# internal_excitation.net
KiCad netlist of a schematic drawn in EAGLE
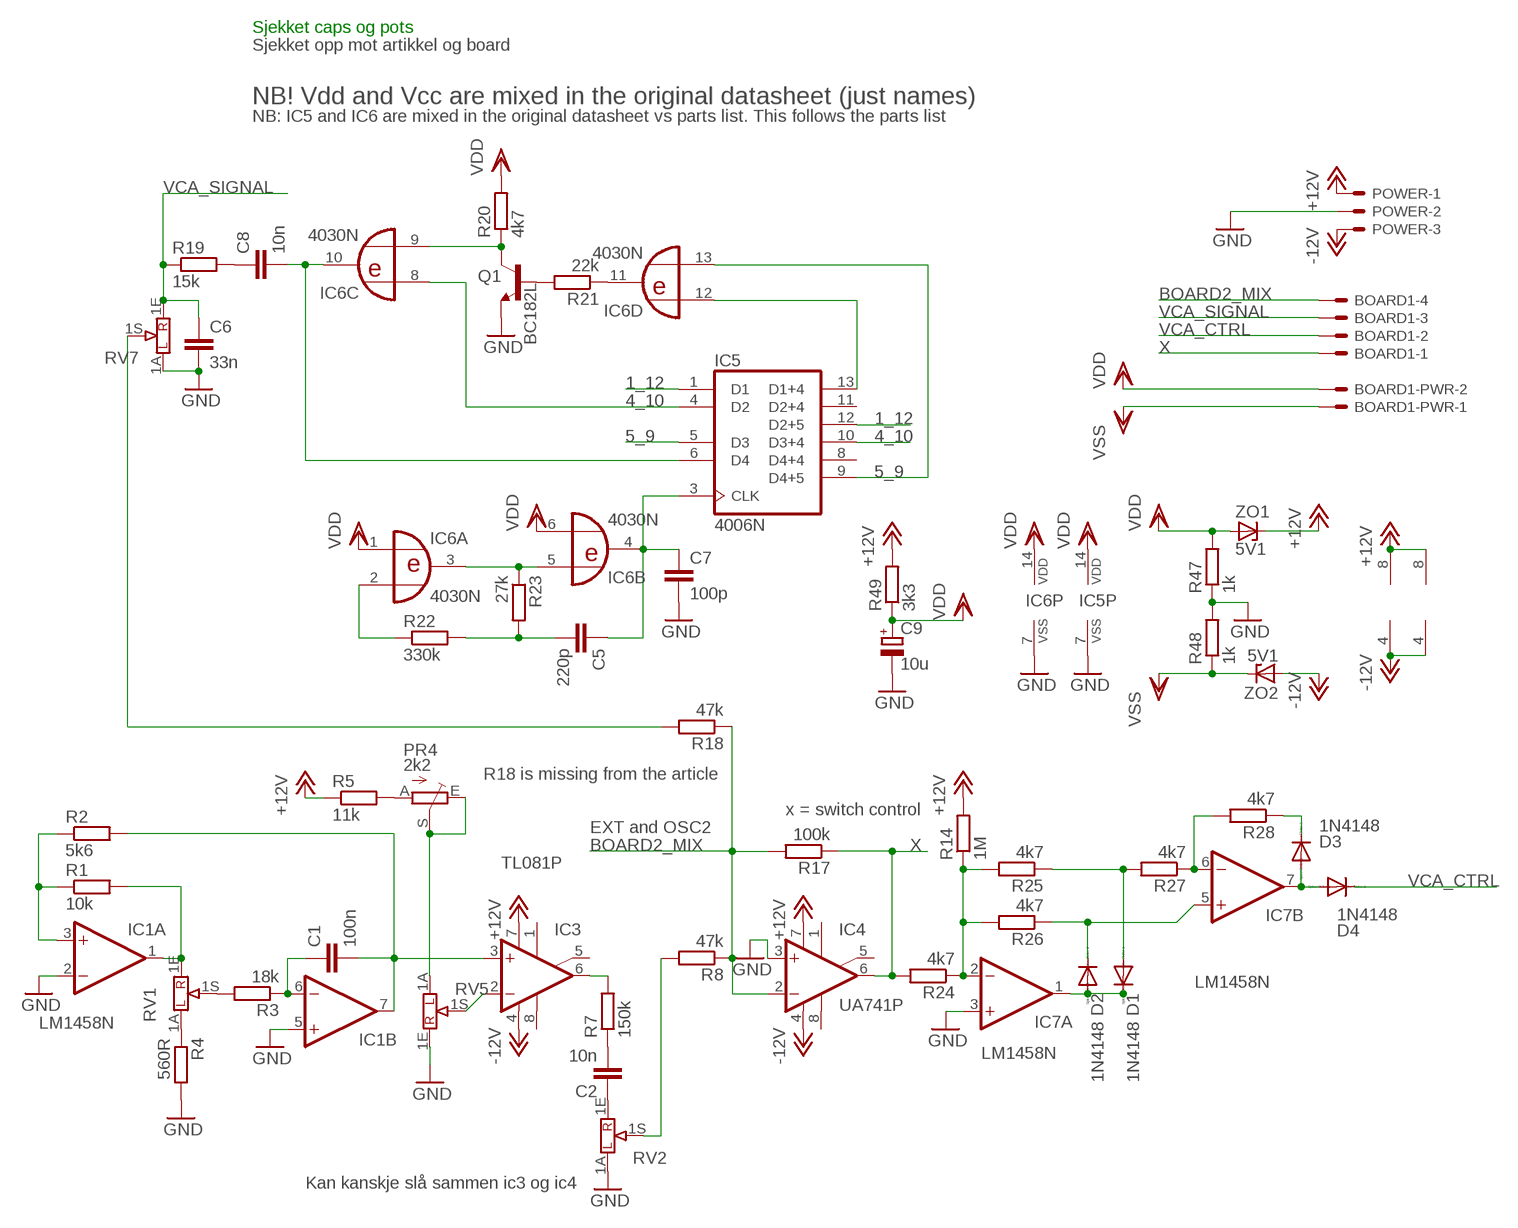
[diagram p0: schematic, sheet 1]

(export (version "E")
  (design (tool "Eeschema 10.0.6"))
  (components
    (comp (ref "BOARD1")
      (value "22-23-2041")
      (footprint "eagle-import:22-23-2041")
      (fields (field (name "MF") "MOLEX"))
      (libsource (lib "eagle-import") (part "22-23-2041"))
    )
    (comp (ref "BOARD1-PWR")
      (value "22-23-2021")
      (footprint "eagle-import:22-23-2021")
      (fields (field (name "MF") "MOLEX"))
      (libsource (lib "eagle-import") (part "22-23-2021"))
    )
    (comp (ref "C1")
      (value "100n")
      (footprint "eagle-import:C075-032X103")
      (libsource (lib "eagle-import") (part "C-EU075-032X103"))
    )
    (comp (ref "C2")
      (value "10n")
      (footprint "eagle-import:C025-025X050")
      (libsource (lib "eagle-import") (part "C-EU025-025X050"))
    )
    (comp (ref "C5")
      (value "220p")
      (footprint "eagle-import:C025-025X050")
      (libsource (lib "eagle-import") (part "C-EU025-025X050"))
    )
    (comp (ref "C6")
      (value "33n")
      (footprint "eagle-import:C075-032X103")
      (libsource (lib "eagle-import") (part "C-EU075-032X103"))
    )
    (comp (ref "C7")
      (value "100p")
      (footprint "eagle-import:C025-025X050")
      (libsource (lib "eagle-import") (part "C-EU025-025X050"))
    )
    (comp (ref "C8")
      (value "10n")
      (footprint "eagle-import:C075-032X103")
      (libsource (lib "eagle-import") (part "C-EU075-032X103"))
    )
    (comp (ref "C9")
      (value "10u")
      (footprint "eagle-import:E2,5-5")
      (libsource (lib "eagle-import") (part "CPOL-EUE2.5-5"))
    )
    (comp (ref "D1")
      (value "1N4148")
      (footprint "eagle-import:DO35-5J")
      (libsource (lib "eagle-import") (part "1N4148DOJ35-5"))
    )
    (comp (ref "D2")
      (value "1N4148")
      (footprint "eagle-import:DO35-5J")
      (libsource (lib "eagle-import") (part "1N4148DOJ35-5"))
    )
    (comp (ref "D3")
      (value "1N4148")
      (footprint "eagle-import:DO35-5J")
      (libsource (lib "eagle-import") (part "1N4148DOJ35-5"))
    )
    (comp (ref "D4")
      (value "1N4148")
      (footprint "eagle-import:DO35-5J")
      (libsource (lib "eagle-import") (part "1N4148DOJ35-5"))
    )
    (comp (ref "IC1")
      (value "LM1458N")
      (footprint "eagle-import:DIL08")
      (libsource (lib "eagle-import") (part "1458NLM"))
    )
    (comp (ref "IC3")
      (value "TL081P")
      (footprint "eagle-import:DIL08")
      (libsource (lib "eagle-import") (part "TL081P"))
    )
    (comp (ref "IC4")
      (value "UA741P")
      (footprint "eagle-import:DIL08")
      (libsource (lib "eagle-import") (part "741PUA"))
    )
    (comp (ref "IC5")
      (value "4006N")
      (footprint "eagle-import:DIL14")
      (libsource (lib "eagle-import") (part "4006N"))
    )
    (comp (ref "IC6")
      (value "4030N")
      (footprint "eagle-import:DIL14")
      (libsource (lib "eagle-import") (part "4030N"))
    )
    (comp (ref "IC7")
      (value "LM1458N")
      (footprint "eagle-import:DIL08")
      (libsource (lib "eagle-import") (part "1458NLM"))
    )
    (comp (ref "POWER")
      (value "KK-156-3")
      (footprint "eagle-import:KK-156-3")
      (libsource (lib "eagle-import") (part "KK-156-3"))
    )
    (comp (ref "PR4")
      (value "2k2")
      (footprint "eagle-import:CA9V")
      (libsource (lib "eagle-import") (part "TRIM_EU-CA9V"))
    )
    (comp (ref "Q1")
      (value "BC182L")
      (footprint "eagle-import:TO92-ECB")
      (libsource (lib "eagle-import") (part "-NPN-TO92-ECB"))
    )
    (comp (ref "R1")
      (value "10k")
      (footprint "eagle-import:0207_7")
      (libsource (lib "eagle-import") (part "R-EU_0207/7"))
    )
    (comp (ref "R2")
      (value "5k6")
      (footprint "eagle-import:0207_7")
      (libsource (lib "eagle-import") (part "R-EU_0207/7"))
    )
    (comp (ref "R3")
      (value "18k")
      (footprint "eagle-import:0207_7")
      (libsource (lib "eagle-import") (part "R-EU_0207/7"))
    )
    (comp (ref "R4")
      (value "560R")
      (footprint "eagle-import:0207_7")
      (libsource (lib "eagle-import") (part "R-EU_0207/7"))
    )
    (comp (ref "R5")
      (value "11k")
      (footprint "eagle-import:0207_7")
      (libsource (lib "eagle-import") (part "R-EU_0207/7"))
    )
    (comp (ref "R7")
      (value "150k")
      (footprint "eagle-import:0207_7")
      (libsource (lib "eagle-import") (part "R-EU_0207/7"))
    )
    (comp (ref "R8")
      (value "47k")
      (footprint "eagle-import:0207_7")
      (libsource (lib "eagle-import") (part "R-EU_0207/7"))
    )
    (comp (ref "R14")
      (value "1M")
      (footprint "eagle-import:0207_7")
      (libsource (lib "eagle-import") (part "R-EU_0207/7"))
    )
    (comp (ref "R17")
      (value "100k")
      (footprint "eagle-import:0207_7")
      (libsource (lib "eagle-import") (part "R-EU_0207/7"))
    )
    (comp (ref "R18")
      (value "47k")
      (footprint "eagle-import:0207_7")
      (libsource (lib "eagle-import") (part "R-EU_0207/7"))
    )
    (comp (ref "R19")
      (value "15k")
      (footprint "eagle-import:0207_7")
      (libsource (lib "eagle-import") (part "R-EU_0207/7"))
    )
    (comp (ref "R20")
      (value "4k7")
      (footprint "eagle-import:0207_7")
      (libsource (lib "eagle-import") (part "R-EU_0207/7"))
    )
    (comp (ref "R21")
      (value "22k")
      (footprint "eagle-import:0207_7")
      (libsource (lib "eagle-import") (part "R-EU_0207/7"))
    )
    (comp (ref "R22")
      (value "330k")
      (footprint "eagle-import:0207_7")
      (libsource (lib "eagle-import") (part "R-EU_0207/7"))
    )
    (comp (ref "R23")
      (value "27k")
      (footprint "eagle-import:0207_7")
      (libsource (lib "eagle-import") (part "R-EU_0207/7"))
    )
    (comp (ref "R24")
      (value "4k7")
      (footprint "eagle-import:0207_7")
      (libsource (lib "eagle-import") (part "R-EU_0207/7"))
    )
    (comp (ref "R25")
      (value "4k7")
      (footprint "eagle-import:0207_7")
      (libsource (lib "eagle-import") (part "R-EU_0207/7"))
    )
    (comp (ref "R26")
      (value "4k7")
      (footprint "eagle-import:0207_7")
      (libsource (lib "eagle-import") (part "R-EU_0207/7"))
    )
    (comp (ref "R27")
      (value "4k7")
      (footprint "eagle-import:0207_7")
      (libsource (lib "eagle-import") (part "R-EU_0207/7"))
    )
    (comp (ref "R28")
      (value "4k7")
      (footprint "eagle-import:0207_7")
      (libsource (lib "eagle-import") (part "R-EU_0207/7"))
    )
    (comp (ref "R47")
      (value "1k")
      (footprint "eagle-import:0207_7")
      (libsource (lib "eagle-import") (part "R-EU_0207/7"))
    )
    (comp (ref "R48")
      (value "1k")
      (footprint "eagle-import:0207_7")
      (libsource (lib "eagle-import") (part "R-EU_0207/7"))
    )
    (comp (ref "R49")
      (value "3k3")
      (footprint "eagle-import:0207_7")
      (libsource (lib "eagle-import") (part "R-EU_0207/7"))
    )
    (comp (ref "RV1")
      (value "10k log")
      (footprint "eagle-import:POT16_W_BRACKET")
      (libsource (lib "eagle-import") (part "POT16_W_BRACKET{dblquote}{dblquote}"))
    )
    (comp (ref "RV2")
      (value "10k log")
      (footprint "eagle-import:POT16_W_BRACKET")
      (libsource (lib "eagle-import") (part "POT16_W_BRACKET{dblquote}{dblquote}"))
    )
    (comp (ref "RV5")
      (value "10k")
      (footprint "eagle-import:POT16_W_BRACKET")
      (libsource (lib "eagle-import") (part "POT16_W_BRACKET{dblquote}{dblquote}"))
    )
    (comp (ref "RV7")
      (value "10k")
      (footprint "eagle-import:POT16_W_BRACKET")
      (libsource (lib "eagle-import") (part "POT16_W_BRACKET{dblquote}{dblquote}"))
    )
    (comp (ref "ZO1")
      (value "5V1")
      (footprint "eagle-import:ZDIO-5")
      (libsource (lib "eagle-import") (part "ZENER-DIODEZD-5"))
    )
    (comp (ref "ZO2")
      (value "5V1")
      (footprint "eagle-import:ZDIO-5")
      (libsource (lib "eagle-import") (part "ZENER-DIODEZD-5"))
    )
  )
  (nets
    (net (code "1") (name "+12V") (class "Default")
      (node (ref "IC1") (pin "8") (pinfunction "V+_8") (pintype "power_in"))
      (node (ref "IC3") (pin "7") (pinfunction "V+_7") (pintype "power_in"))
      (node (ref "IC4") (pin "7") (pinfunction "V+_7") (pintype "power_in"))
      (node (ref "IC7") (pin "8") (pinfunction "V+_8") (pintype "power_in"))
      (node (ref "POWER") (pin "1") (pinfunction "S_1") (pintype "passive"))
      (node (ref "R14") (pin "2") (pinfunction "2_2") (pintype "passive"))
      (node (ref "R49") (pin "2") (pinfunction "2_2") (pintype "passive"))
      (node (ref "R5") (pin "1") (pinfunction "1_1") (pintype "passive"))
      (node (ref "ZO1") (pin "C") (pinfunction "C_C") (pintype "passive"))
    )
    (net (code "2") (name "-12V") (class "Default")
      (node (ref "IC1") (pin "4") (pinfunction "V-_4") (pintype "power_in"))
      (node (ref "IC3") (pin "4") (pinfunction "V-_4") (pintype "power_in"))
      (node (ref "IC4") (pin "4") (pinfunction "V-_4") (pintype "power_in"))
      (node (ref "IC7") (pin "4") (pinfunction "V-_4") (pintype "power_in"))
      (node (ref "POWER") (pin "3") (pinfunction "S_3") (pintype "passive"))
      (node (ref "ZO2") (pin "A") (pinfunction "A_A") (pintype "passive"))
    )
    (net (code "3") (name "/1_12") (class "Default")
      (node (ref "IC5") (pin "1") (pinfunction "D1_1") (pintype "input"))
      (node (ref "IC5") (pin "12") (pinfunction "D2+5_12") (pintype "output"))
    )
    (net (code "4") (name "/4_10") (class "Default")
      (node (ref "IC5") (pin "10") (pinfunction "D3+4_10") (pintype "output"))
      (node (ref "IC5") (pin "4") (pinfunction "D2_4") (pintype "input"))
      (node (ref "IC6") (pin "8") (pinfunction "I0_8") (pintype "input"))
    )
    (net (code "5") (name "/5_9") (class "Default")
      (node (ref "IC5") (pin "5") (pinfunction "D3_5") (pintype "input"))
      (node (ref "IC5") (pin "9") (pinfunction "D4+5_9") (pintype "output"))
      (node (ref "IC6") (pin "13") (pinfunction "I1_13") (pintype "input"))
    )
    (net (code "6") (name "/BOARD2_MIX") (class "Default")
      (node (ref "BOARD1") (pin "4") (pinfunction "S_4") (pintype "passive"))
      (node (ref "IC4") (pin "2") (pinfunction "-IN_2") (pintype "input"))
      (node (ref "R17") (pin "2") (pinfunction "2_2") (pintype "passive"))
      (node (ref "R18") (pin "1") (pinfunction "1_1") (pintype "passive"))
      (node (ref "R8") (pin "1") (pinfunction "1_1") (pintype "passive"))
    )
    (net (code "7") (name "/VCA_CTRL") (class "Default")
      (node (ref "BOARD1") (pin "2") (pinfunction "S_2") (pintype "passive"))
      (node (ref "D4") (pin "C") (pinfunction "C_C") (pintype "passive"))
    )
    (net (code "8") (name "/VCA_SIGNAL") (class "Default")
      (node (ref "BOARD1") (pin "3") (pinfunction "S_3") (pintype "passive"))
      (node (ref "C6") (pin "1") (pinfunction "1_1") (pintype "passive"))
      (node (ref "R19") (pin "1") (pinfunction "1_1") (pintype "passive"))
      (node (ref "RV7") (pin "1E") (pinfunction "1E_1E") (pintype "passive"))
    )
    (net (code "9") (name "/X") (class "Default")
      (node (ref "BOARD1") (pin "1") (pinfunction "S_1") (pintype "passive"))
      (node (ref "IC4") (pin "6") (pinfunction "OUT_6") (pintype "output"))
      (node (ref "R17") (pin "1") (pinfunction "1_1") (pintype "passive"))
      (node (ref "R24") (pin "2") (pinfunction "2_2") (pintype "passive"))
    )
    (net (code "10") (name "GND") (class "Default")
      (node (ref "C6") (pin "2") (pinfunction "2_2") (pintype "passive"))
      (node (ref "C7") (pin "2") (pinfunction "2_2") (pintype "passive"))
      (node (ref "C9") (pin "-") (pinfunction "-_-") (pintype "passive"))
      (node (ref "IC1") (pin "2") (pinfunction "-IN_2") (pintype "input"))
      (node (ref "IC1") (pin "5") (pinfunction "+IN_5") (pintype "input"))
      (node (ref "IC4") (pin "3") (pinfunction "+IN_3") (pintype "input"))
      (node (ref "IC5") (pin "7") (pinfunction "VSS_7") (pintype "power_in"))
      (node (ref "IC6") (pin "7") (pinfunction "VSS_7") (pintype "power_in"))
      (node (ref "IC7") (pin "3") (pinfunction "+IN_3") (pintype "input"))
      (node (ref "POWER") (pin "2") (pinfunction "S_2") (pintype "passive"))
      (node (ref "Q1") (pin "E") (pinfunction "E_E") (pintype "passive"))
      (node (ref "R4") (pin "2") (pinfunction "2_2") (pintype "passive"))
      (node (ref "R47") (pin "1") (pinfunction "1_1") (pintype "passive"))
      (node (ref "R48") (pin "2") (pinfunction "2_2") (pintype "passive"))
      (node (ref "RV2") (pin "1A") (pinfunction "1A_1A") (pintype "passive"))
      (node (ref "RV5") (pin "1E") (pinfunction "1E_1E") (pintype "passive"))
      (node (ref "RV7") (pin "1A") (pinfunction "1A_1A") (pintype "passive"))
    )
    (net (code "11") (name "Net-(C2-Pad1)") (class "Default")
      (node (ref "C2") (pin "1") (pinfunction "1_1") (pintype "passive"))
      (node (ref "RV2") (pin "1E") (pinfunction "1E_1E") (pintype "passive"))
    )
    (net (code "12") (name "Net-(C2-Pad2)") (class "Default")
      (node (ref "C2") (pin "2") (pinfunction "2_2") (pintype "passive"))
      (node (ref "R7") (pin "1") (pinfunction "1_1") (pintype "passive"))
    )
    (net (code "13") (name "Net-(C5-Pad2)") (class "Default")
      (node (ref "C5") (pin "2") (pinfunction "2_2") (pintype "passive"))
      (node (ref "R22") (pin "2") (pinfunction "2_2") (pintype "passive"))
      (node (ref "R23") (pin "2") (pinfunction "2_2") (pintype "passive"))
    )
    (net (code "14") (name "Net-(C8-Pad1)") (class "Default")
      (node (ref "C8") (pin "1") (pinfunction "1_1") (pintype "passive"))
      (node (ref "R19") (pin "2") (pinfunction "2_2") (pintype "passive"))
    )
    (net (code "15") (name "Net-(D1-PadA)") (class "Default")
      (node (ref "D1") (pin "A") (pinfunction "A_A") (pintype "passive"))
      (node (ref "R25") (pin "1") (pinfunction "1_1") (pintype "passive"))
      (node (ref "R27") (pin "2") (pinfunction "2_2") (pintype "passive"))
    )
    (net (code "16") (name "Net-(D3-PadC)") (class "Default")
      (node (ref "D3") (pin "C") (pinfunction "C_C") (pintype "passive"))
      (node (ref "R28") (pin "1") (pinfunction "1_1") (pintype "passive"))
    )
    (net (code "17") (name "Net-(IC1A-+IN)") (class "Default")
      (node (ref "IC1") (pin "3") (pinfunction "+IN_3") (pintype "input"))
      (node (ref "R1") (pin "1") (pinfunction "1_1") (pintype "passive"))
      (node (ref "R2") (pin "1") (pinfunction "1_1") (pintype "passive"))
    )
    (net (code "18") (name "Net-(IC1A-OUT)") (class "Default")
      (node (ref "IC1") (pin "1") (pinfunction "OUT_1") (pintype "output"))
      (node (ref "R1") (pin "2") (pinfunction "2_2") (pintype "passive"))
      (node (ref "RV1") (pin "1E") (pinfunction "1E_1E") (pintype "passive"))
    )
    (net (code "19") (name "Net-(IC1B--IN)") (class "Default")
      (node (ref "C1") (pin "1") (pinfunction "1_1") (pintype "passive"))
      (node (ref "IC1") (pin "6") (pinfunction "-IN_6") (pintype "input"))
      (node (ref "R3") (pin "1") (pinfunction "1_1") (pintype "passive"))
    )
    (net (code "20") (name "Net-(IC1B-OUT)") (class "Default")
      (node (ref "C1") (pin "2") (pinfunction "2_2") (pintype "passive"))
      (node (ref "IC1") (pin "7") (pinfunction "OUT_7") (pintype "output"))
      (node (ref "IC3") (pin "3") (pinfunction "+IN_3") (pintype "input"))
      (node (ref "R2") (pin "2") (pinfunction "2_2") (pintype "passive"))
    )
    (net (code "21") (name "Net-(IC3--IN)") (class "Default")
      (node (ref "IC3") (pin "2") (pinfunction "-IN_2") (pintype "input"))
      (node (ref "RV5") (pin "1S") (pinfunction "1S_1S") (pintype "passive"))
    )
    (net (code "22") (name "Net-(IC3-OUT)") (class "Default")
      (node (ref "IC3") (pin "6") (pinfunction "OUT_6") (pintype "output"))
      (node (ref "R7") (pin "2") (pinfunction "2_2") (pintype "passive"))
    )
    (net (code "23") (name "Net-(IC5A-CLK)") (class "Default")
      (node (ref "C5") (pin "1") (pinfunction "1_1") (pintype "passive"))
      (node (ref "C7") (pin "1") (pinfunction "1_1") (pintype "passive"))
      (node (ref "IC5") (pin "3") (pinfunction "CLK_3") (pintype "input"))
      (node (ref "IC6") (pin "4") (pinfunction "O_4") (pintype "output"))
    )
    (net (code "24") (name "Net-(IC5A-D1+4)") (class "Default")
      (node (ref "IC5") (pin "13") (pinfunction "D1+4_13") (pintype "output"))
      (node (ref "IC6") (pin "12") (pinfunction "I0_12") (pintype "input"))
    )
    (net (code "25") (name "Net-(IC5A-D4)") (class "Default")
      (node (ref "C8") (pin "2") (pinfunction "2_2") (pintype "passive"))
      (node (ref "IC5") (pin "6") (pinfunction "D4_6") (pintype "input"))
      (node (ref "IC6") (pin "10") (pinfunction "O_10") (pintype "output"))
    )
    (net (code "26") (name "Net-(IC6A-I1)") (class "Default")
      (node (ref "IC6") (pin "2") (pinfunction "I1_2") (pintype "input"))
      (node (ref "R22") (pin "1") (pinfunction "1_1") (pintype "passive"))
    )
    (net (code "27") (name "Net-(IC6A-O)") (class "Default")
      (node (ref "IC6") (pin "3") (pinfunction "O_3") (pintype "output"))
      (node (ref "IC6") (pin "5") (pinfunction "I0_5") (pintype "input"))
      (node (ref "R23") (pin "1") (pinfunction "1_1") (pintype "passive"))
    )
    (net (code "28") (name "Net-(IC6C-I1)") (class "Default")
      (node (ref "IC6") (pin "9") (pinfunction "I1_9") (pintype "input"))
      (node (ref "Q1") (pin "C") (pinfunction "C_C") (pintype "passive"))
      (node (ref "R20") (pin "1") (pinfunction "1_1") (pintype "passive"))
    )
    (net (code "29") (name "Net-(IC6D-O)") (class "Default")
      (node (ref "IC6") (pin "11") (pinfunction "O_11") (pintype "output"))
      (node (ref "R21") (pin "1") (pinfunction "1_1") (pintype "passive"))
    )
    (net (code "30") (name "Net-(IC7A--IN)") (class "Default")
      (node (ref "IC7") (pin "2") (pinfunction "-IN_2") (pintype "input"))
      (node (ref "R14") (pin "1") (pinfunction "1_1") (pintype "passive"))
      (node (ref "R24") (pin "1") (pinfunction "1_1") (pintype "passive"))
      (node (ref "R25") (pin "2") (pinfunction "2_2") (pintype "passive"))
      (node (ref "R26") (pin "2") (pinfunction "2_2") (pintype "passive"))
    )
    (net (code "31") (name "Net-(IC7A-OUT)") (class "Default")
      (node (ref "D1") (pin "C") (pinfunction "C_C") (pintype "passive"))
      (node (ref "D2") (pin "A") (pinfunction "A_A") (pintype "passive"))
      (node (ref "IC7") (pin "1") (pinfunction "OUT_1") (pintype "output"))
    )
    (net (code "32") (name "Net-(IC7B-+IN)") (class "Default")
      (node (ref "D2") (pin "C") (pinfunction "C_C") (pintype "passive"))
      (node (ref "IC7") (pin "5") (pinfunction "+IN_5") (pintype "input"))
      (node (ref "R26") (pin "1") (pinfunction "1_1") (pintype "passive"))
    )
    (net (code "33") (name "Net-(IC7B--IN)") (class "Default")
      (node (ref "IC7") (pin "6") (pinfunction "-IN_6") (pintype "input"))
      (node (ref "R27") (pin "1") (pinfunction "1_1") (pintype "passive"))
      (node (ref "R28") (pin "2") (pinfunction "2_2") (pintype "passive"))
    )
    (net (code "34") (name "Net-(IC7B-OUT)") (class "Default")
      (node (ref "D3") (pin "A") (pinfunction "A_A") (pintype "passive"))
      (node (ref "D4") (pin "A") (pinfunction "A_A") (pintype "passive"))
      (node (ref "IC7") (pin "7") (pinfunction "OUT_7") (pintype "output"))
    )
    (net (code "35") (name "Net-(PR4-PadA)") (class "Default")
      (node (ref "PR4") (pin "A") (pinfunction "A_A") (pintype "passive"))
      (node (ref "R5") (pin "2") (pinfunction "2_2") (pintype "passive"))
    )
    (net (code "36") (name "Net-(PR4-PadE)") (class "Default")
      (node (ref "PR4") (pin "E") (pinfunction "E_E") (pintype "passive"))
      (node (ref "PR4") (pin "S") (pinfunction "S_S") (pintype "passive"))
      (node (ref "RV5") (pin "1A") (pinfunction "1A_1A") (pintype "passive"))
    )
    (net (code "37") (name "Net-(Q1-PadB)") (class "Default")
      (node (ref "Q1") (pin "B") (pinfunction "B_B") (pintype "passive"))
      (node (ref "R21") (pin "2") (pinfunction "2_2") (pintype "passive"))
    )
    (net (code "38") (name "Net-(R3-Pad2)") (class "Default")
      (node (ref "R3") (pin "2") (pinfunction "2_2") (pintype "passive"))
      (node (ref "RV1") (pin "1S") (pinfunction "1S_1S") (pintype "passive"))
    )
    (net (code "39") (name "Net-(R4-Pad1)") (class "Default")
      (node (ref "R4") (pin "1") (pinfunction "1_1") (pintype "passive"))
      (node (ref "RV1") (pin "1A") (pinfunction "1A_1A") (pintype "passive"))
    )
    (net (code "40") (name "Net-(R8-Pad2)") (class "Default")
      (node (ref "R8") (pin "2") (pinfunction "2_2") (pintype "passive"))
      (node (ref "RV2") (pin "1S") (pinfunction "1S_1S") (pintype "passive"))
    )
    (net (code "41") (name "Net-(R18-Pad2)") (class "Default")
      (node (ref "R18") (pin "2") (pinfunction "2_2") (pintype "passive"))
      (node (ref "RV7") (pin "1S") (pinfunction "1S_1S") (pintype "passive"))
    )
    (net (code "42") (name "VDD") (class "Default")
      (node (ref "BOARD1-PWR") (pin "2") (pinfunction "S_2") (pintype "passive"))
      (node (ref "C9") (pin "+") (pinfunction "+_+") (pintype "passive"))
      (node (ref "IC5") (pin "14") (pinfunction "VDD_14") (pintype "power_in"))
      (node (ref "IC6") (pin "1") (pinfunction "I0_1") (pintype "input"))
      (node (ref "IC6") (pin "14") (pinfunction "VDD_14") (pintype "power_in"))
      (node (ref "IC6") (pin "6") (pinfunction "I1_6") (pintype "input"))
      (node (ref "R20") (pin "2") (pinfunction "2_2") (pintype "passive"))
      (node (ref "R47") (pin "2") (pinfunction "2_2") (pintype "passive"))
      (node (ref "R49") (pin "1") (pinfunction "1_1") (pintype "passive"))
      (node (ref "ZO1") (pin "A") (pinfunction "A_A") (pintype "passive"))
    )
    (net (code "43") (name "VSS") (class "Default")
      (node (ref "BOARD1-PWR") (pin "1") (pinfunction "S_1") (pintype "passive"))
      (node (ref "R48") (pin "1") (pinfunction "1_1") (pintype "passive"))
      (node (ref "ZO2") (pin "C") (pinfunction "C_C") (pintype "passive"))
    )
    (net (code "44") (name "unconnected-(IC3-ON1-Pad1)") (class "Default")
      (node (ref "IC3") (pin "1") (pinfunction "ON1_1") (pintype "passive"))
    )
    (net (code "45") (name "unconnected-(IC3-ON2-Pad5)") (class "Default")
      (node (ref "IC3") (pin "5") (pinfunction "ON2_5") (pintype "passive"))
    )
    (net (code "46") (name "unconnected-(IC3-OPT-Pad8)") (class "Default")
      (node (ref "IC3") (pin "8") (pinfunction "OPT_8") (pintype "passive"))
    )
    (net (code "47") (name "unconnected-(IC4-ON1-Pad1)") (class "Default")
      (node (ref "IC4") (pin "1") (pinfunction "ON1_1") (pintype "passive"))
    )
    (net (code "48") (name "unconnected-(IC4-ON2-Pad5)") (class "Default")
      (node (ref "IC4") (pin "5") (pinfunction "ON2_5") (pintype "passive"))
    )
    (net (code "49") (name "unconnected-(IC4-OPT-Pad8)") (class "Default")
      (node (ref "IC4") (pin "8") (pinfunction "OPT_8") (pintype "passive"))
    )
    (net (code "50") (name "unconnected-(IC5A-D2+4-Pad11)") (class "Default")
      (node (ref "IC5") (pin "11") (pinfunction "D2+4_11") (pintype "output"))
    )
    (net (code "51") (name "unconnected-(IC5A-D4+4-Pad8)") (class "Default")
      (node (ref "IC5") (pin "8") (pinfunction "D4+4_8") (pintype "output"))
    )
  )
)
